# CPU.net
KiCad netlist of a schematic drawn in Altium Designer
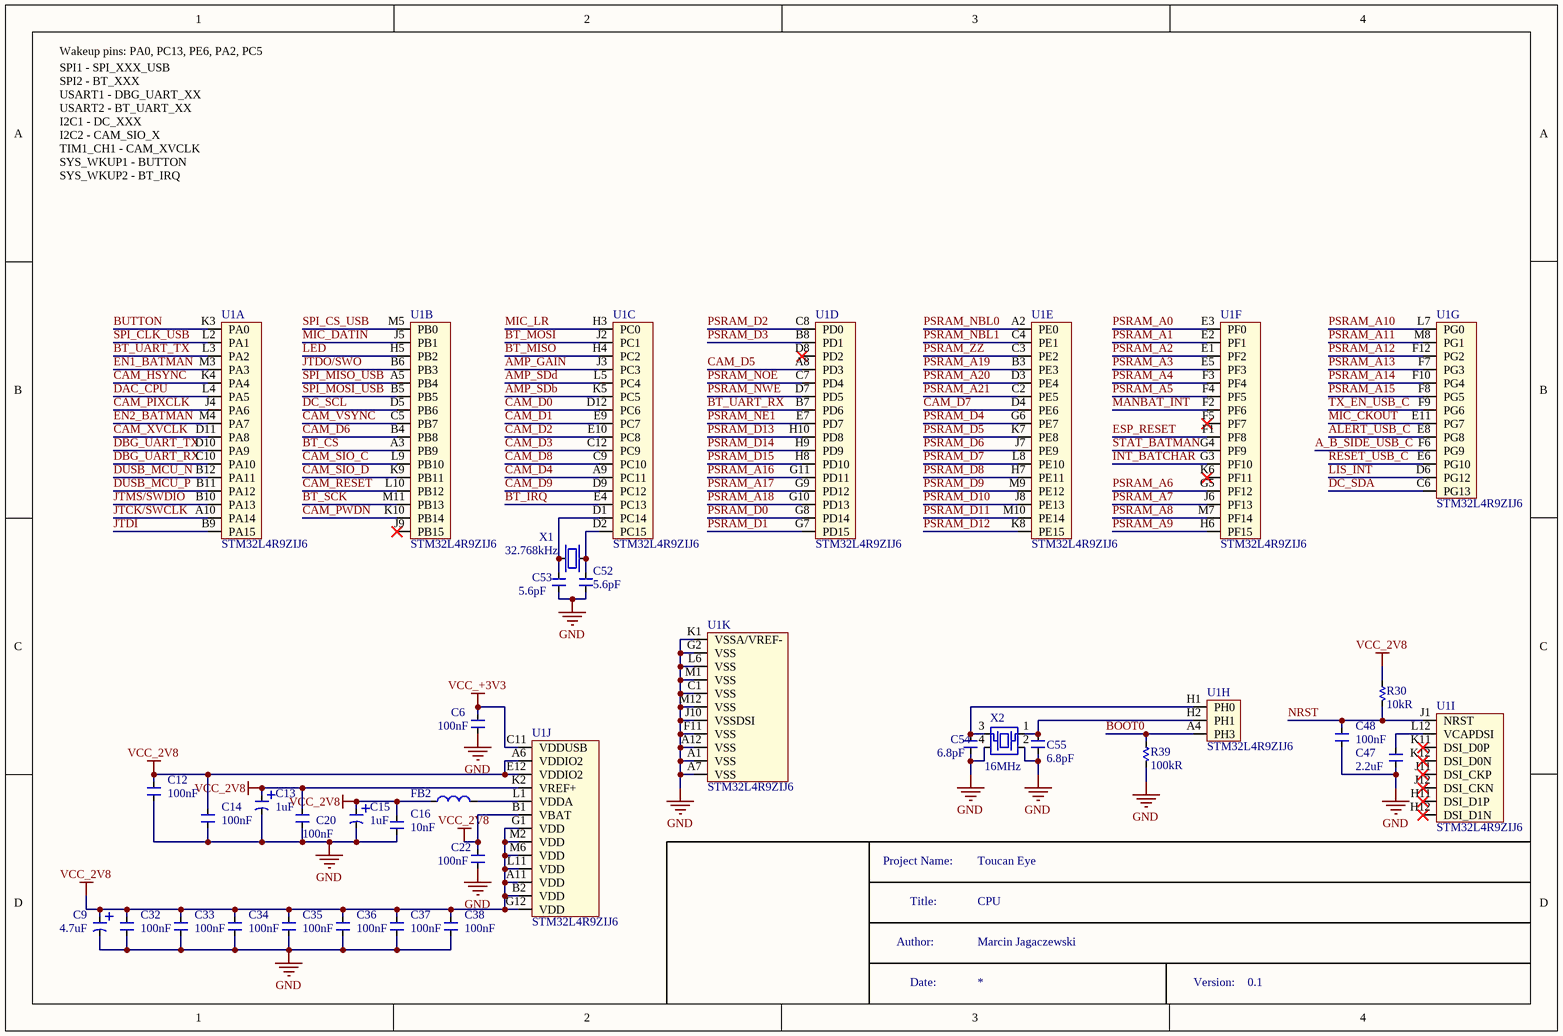
[diagram p0: CPU.SchDoc]

(export (version "E")
  (design (tool "Eeschema 10.0.6"))
  (components
    (comp (ref "C6")
      (value "C0201_100n_GRM033R6YA104KE14D")
      (footprint "C_0201")
      (description "Multilayer Ceramic Capacitors MLCC - SMD/SMT 0201 0.10uF 35volts *Derate Voltage/Temp")
      (fields
        (field (name "MANUFACTURER") "Murata")
        (field (name "MANUFACTURER PART NUMBER") "GRM033R6YA104KE14D")
        (field (name "CAPACITANCE") "100nF")
      )
      (libsource (lib "CAP") (part "C0201_100n_GRM033R6YA104KE14D"))
    )
    (comp (ref "C9")
      (value "C_4.7u_TANTAL_A_TAJA475K016UNJ")
      (footprint "C_3216")
      (description "TANTALUM CHIPS, TAN")
      (fields
        (field (name "MANUFACTURER") "Kyocera AVX")
        (field (name "MANUFACTURER PART NUMBER") "TAJA475K016UNJ")
        (field (name "CAPACITANCE") "4.7uF")
      )
      (libsource (lib "CAP") (part "C_4.7u_TANTAL_A_TAJA475K016UNJ"))
    )
    (comp (ref "C12")
      (value "C0201_100n_GRM033R6YA104KE14D")
      (footprint "C_0201")
      (description "Multilayer Ceramic Capacitors MLCC - SMD/SMT 0201 0.10uF 35volts *Derate Voltage/Temp")
      (fields
        (field (name "MANUFACTURER") "Murata")
        (field (name "MANUFACTURER PART NUMBER") "GRM033R6YA104KE14D")
        (field (name "CAPACITANCE") "100nF")
      )
      (libsource (lib "CAP") (part "C0201_100n_GRM033R6YA104KE14D"))
    )
    (comp (ref "C13")
      (value "C_1u_TANTAL_A_293D105X0025A2TE3")
      (footprint "C_3216")
      (description "CAP TANT 1UF 25V 20% 1206")
      (fields
        (field (name "MANUFACTURER") "Vishay Sprague")
        (field (name "MANUFACTURER PART NUMBER") "293D105X0025A2TE3")
        (field (name "CAPACITANCE") "1uF")
      )
      (libsource (lib "CAP") (part "C_1u_TANTAL_A_293D105X0025A2TE3"))
    )
    (comp (ref "C14")
      (value "C0201_100n_GRM033R6YA104KE14D")
      (footprint "C_0201")
      (description "Multilayer Ceramic Capacitors MLCC - SMD/SMT 0201 0.10uF 35volts *Derate Voltage/Temp")
      (fields
        (field (name "MANUFACTURER") "Murata")
        (field (name "MANUFACTURER PART NUMBER") "GRM033R6YA104KE14D")
        (field (name "CAPACITANCE") "100nF")
      )
      (libsource (lib "CAP") (part "C0201_100n_GRM033R6YA104KE14D"))
    )
    (comp (ref "C15")
      (value "C_1u_TANTAL_A_293D105X0025A2TE3")
      (footprint "C_3216")
      (description "CAP TANT 1UF 25V 20% 1206")
      (fields
        (field (name "MANUFACTURER") "Vishay Sprague")
        (field (name "MANUFACTURER PART NUMBER") "293D105X0025A2TE3")
        (field (name "CAPACITANCE") "1uF")
      )
      (libsource (lib "CAP") (part "C_1u_TANTAL_A_293D105X0025A2TE3"))
    )
    (comp (ref "C16")
      (value "C0201_10n_CGA1A2X7R1A103K030BA")
      (footprint "C_0201")
      (fields
        (field (name "MANUFACTURER") "TDK")
        (field (name "MANUFACTURER PART NUMBER") "CGA1A2X7R1A103K030BA")
        (field (name "TOLERANCE") "10%")
        (field (name "CAPACITANCE") "10nF")
      )
      (libsource (lib "CAP") (part "C0201_10n_CGA1A2X7R1A103K030BA"))
    )
    (comp (ref "C20")
      (value "C0201_100n_GRM033R6YA104KE14D")
      (footprint "C_0201")
      (description "Multilayer Ceramic Capacitors MLCC - SMD/SMT 0201 0.10uF 35volts *Derate Voltage/Temp")
      (fields
        (field (name "MANUFACTURER") "Murata")
        (field (name "MANUFACTURER PART NUMBER") "GRM033R6YA104KE14D")
        (field (name "CAPACITANCE") "100nF")
      )
      (libsource (lib "CAP") (part "C0201_100n_GRM033R6YA104KE14D"))
    )
    (comp (ref "C22")
      (value "C0201_100n_GRM033R6YA104KE14D")
      (footprint "C_0201")
      (description "Multilayer Ceramic Capacitors MLCC - SMD/SMT 0201 0.10uF 35volts *Derate Voltage/Temp")
      (fields
        (field (name "MANUFACTURER") "Murata")
        (field (name "MANUFACTURER PART NUMBER") "GRM033R6YA104KE14D")
        (field (name "CAPACITANCE") "100nF")
      )
      (libsource (lib "CAP") (part "C0201_100n_GRM033R6YA104KE14D"))
    )
    (comp (ref "C32")
      (value "C0201_100n_GRM033R6YA104KE14D")
      (footprint "C_0201")
      (description "Multilayer Ceramic Capacitors MLCC - SMD/SMT 0201 0.10uF 35volts *Derate Voltage/Temp")
      (fields
        (field (name "MANUFACTURER") "Murata")
        (field (name "MANUFACTURER PART NUMBER") "GRM033R6YA104KE14D")
        (field (name "CAPACITANCE") "100nF")
      )
      (libsource (lib "CAP") (part "C0201_100n_GRM033R6YA104KE14D"))
    )
    (comp (ref "C33")
      (value "C0201_100n_GRM033R6YA104KE14D")
      (footprint "C_0201")
      (description "Multilayer Ceramic Capacitors MLCC - SMD/SMT 0201 0.10uF 35volts *Derate Voltage/Temp")
      (fields
        (field (name "MANUFACTURER") "Murata")
        (field (name "MANUFACTURER PART NUMBER") "GRM033R6YA104KE14D")
        (field (name "CAPACITANCE") "100nF")
      )
      (libsource (lib "CAP") (part "C0201_100n_GRM033R6YA104KE14D"))
    )
    (comp (ref "C34")
      (value "C0201_100n_GRM033R6YA104KE14D")
      (footprint "C_0201")
      (description "Multilayer Ceramic Capacitors MLCC - SMD/SMT 0201 0.10uF 35volts *Derate Voltage/Temp")
      (fields
        (field (name "MANUFACTURER") "Murata")
        (field (name "MANUFACTURER PART NUMBER") "GRM033R6YA104KE14D")
        (field (name "CAPACITANCE") "100nF")
      )
      (libsource (lib "CAP") (part "C0201_100n_GRM033R6YA104KE14D"))
    )
    (comp (ref "C35")
      (value "C0201_100n_GRM033R6YA104KE14D")
      (footprint "C_0201")
      (description "Multilayer Ceramic Capacitors MLCC - SMD/SMT 0201 0.10uF 35volts *Derate Voltage/Temp")
      (fields
        (field (name "MANUFACTURER") "Murata")
        (field (name "MANUFACTURER PART NUMBER") "GRM033R6YA104KE14D")
        (field (name "CAPACITANCE") "100nF")
      )
      (libsource (lib "CAP") (part "C0201_100n_GRM033R6YA104KE14D"))
    )
    (comp (ref "C36")
      (value "C0201_100n_GRM033R6YA104KE14D")
      (footprint "C_0201")
      (description "Multilayer Ceramic Capacitors MLCC - SMD/SMT 0201 0.10uF 35volts *Derate Voltage/Temp")
      (fields
        (field (name "MANUFACTURER") "Murata")
        (field (name "MANUFACTURER PART NUMBER") "GRM033R6YA104KE14D")
        (field (name "CAPACITANCE") "100nF")
      )
      (libsource (lib "CAP") (part "C0201_100n_GRM033R6YA104KE14D"))
    )
    (comp (ref "C37")
      (value "C0201_100n_GRM033R6YA104KE14D")
      (footprint "C_0201")
      (description "Multilayer Ceramic Capacitors MLCC - SMD/SMT 0201 0.10uF 35volts *Derate Voltage/Temp")
      (fields
        (field (name "MANUFACTURER") "Murata")
        (field (name "MANUFACTURER PART NUMBER") "GRM033R6YA104KE14D")
        (field (name "CAPACITANCE") "100nF")
      )
      (libsource (lib "CAP") (part "C0201_100n_GRM033R6YA104KE14D"))
    )
    (comp (ref "C38")
      (value "C0201_100n_GRM033R6YA104KE14D")
      (footprint "C_0201")
      (description "Multilayer Ceramic Capacitors MLCC - SMD/SMT 0201 0.10uF 35volts *Derate Voltage/Temp")
      (fields
        (field (name "MANUFACTURER") "Murata")
        (field (name "MANUFACTURER PART NUMBER") "GRM033R6YA104KE14D")
        (field (name "CAPACITANCE") "100nF")
      )
      (libsource (lib "CAP") (part "C0201_100n_GRM033R6YA104KE14D"))
    )
    (comp (ref "C47")
      (value "C0402_2.2u_GRT155R61E225KE13D")
      (footprint "C_0402")
      (description "2.2µF 25V Ceramic Capacitor X5R 0402 (1005 Metric) 0.039\" L x 0.020\" W (1.00mm x 0.50mm)")
      (fields
        (field (name "MANUFACTURER") "Murata")
        (field (name "MANUFACTURER PART NUMBER") "GRT155R61E225KE13D")
        (field (name "CAPACITANCE") "2.2uF")
      )
      (libsource (lib "CAP") (part "C0402_2.2u_GRT155R61E225KE13D"))
    )
    (comp (ref "C48")
      (value "C0201_100n_GRM033R6YA104KE14D")
      (footprint "C_0201")
      (description "Multilayer Ceramic Capacitors MLCC - SMD/SMT 0201 0.10uF 35volts *Derate Voltage/Temp")
      (fields
        (field (name "MANUFACTURER") "Murata")
        (field (name "MANUFACTURER PART NUMBER") "GRM033R6YA104KE14D")
        (field (name "CAPACITANCE") "100nF")
      )
      (libsource (lib "CAP") (part "C0201_100n_GRM033R6YA104KE14D"))
    )
    (comp (ref "C52")
      (value "C0201_5.6pF_GRM0335C1H5R6BA01D")
      (footprint "C_0201")
      (description "Multilayer Ceramic Capacitors MLCC - SMD/SMT 0201 5.6pF 50volts C0G +/-0.1pF")
      (fields
        (field (name "MANUFACTURER") "Murata")
        (field (name "MANUFACTURER PART NUMBER") "GRM0335C1H5R6BA01D")
        (field (name "CAPACITANCE") "5.6pF")
      )
      (libsource (lib "CAP") (part "C0201_5.6pF_GRM0335C1H5R6BA01D"))
    )
    (comp (ref "C53")
      (value "C0201_5.6pF_GRM0335C1H5R6BA01D")
      (footprint "C_0201")
      (description "Multilayer Ceramic Capacitors MLCC - SMD/SMT 0201 5.6pF 50volts C0G +/-0.1pF")
      (fields
        (field (name "MANUFACTURER") "Murata")
        (field (name "MANUFACTURER PART NUMBER") "GRM0335C1H5R6BA01D")
        (field (name "CAPACITANCE") "5.6pF")
      )
      (libsource (lib "CAP") (part "C0201_5.6pF_GRM0335C1H5R6BA01D"))
    )
    (comp (ref "C54")
      (value "C0201_6.8pF_GJM0335C1E6R8CB01D")
      (footprint "C_0201")
      (description "CAP CER 6.8PF 25V NP0 0201")
      (fields
        (field (name "MANUFACTURER") "Murata")
        (field (name "MANUFACTURER PART NUMBER") "GJM0335C1E6R8CB01D")
        (field (name "CAPACITANCE") "6.8pF")
      )
      (libsource (lib "CAP") (part "C0201_6.8pF_GJM0335C1E6R8CB01D"))
    )
    (comp (ref "C55")
      (value "C0201_6.8pF_GJM0335C1E6R8CB01D")
      (footprint "C_0201")
      (description "CAP CER 6.8PF 25V NP0 0201")
      (fields
        (field (name "MANUFACTURER") "Murata")
        (field (name "MANUFACTURER PART NUMBER") "GJM0335C1E6R8CB01D")
        (field (name "CAPACITANCE") "6.8pF")
      )
      (libsource (lib "CAP") (part "C0201_6.8pF_GJM0335C1E6R8CB01D"))
    )
    (comp (ref "FB2")
      (value "BLM15AG121SN1D")
      (footprint "L_0402")
      (description "MURATA         BLM15AG121SN1D             FERRITE BEAD, 0.25OHM, 500MA, 0402")
      (fields (field (name "MANUFACTURER") "Murata") (field (name "TOLERANCE") "25%"))
      (libsource (lib "IND") (part "BLM15AG121SN1D"))
    )
    (comp (ref "R30")
      (value "R0201_10k_ERJ-1GNF1002C")
      (footprint "R_0201")
      (description "RESISTOR, 0201, 0.05W, 1%, 10K")
      (fields
        (field (name "MANUFACTURER") "Panasonic ECG")
        (field (name "MANUFACTURER PART NUMBER") "ERJ-1GNF1002C")
        (field (name "RESISTANCE") "10kR")
      )
      (libsource (lib "RES") (part "R0201_10k_ERJ-1GNF1002C"))
    )
    (comp (ref "R39")
      (value "R0201_100k_CRCW0201100KJN-ED")
      (footprint "R_0201")
      (description "RES SMD 100K OHM 5% 1/20W 0201")
      (fields
        (field (name "MANUFACTURER") "Vishay Dale")
        (field (name "MANUFACTURER PART NUMBER") "CRCW0201100KJN-ED")
        (field (name "RESISTANCE") "100kR")
      )
      (libsource (lib "RES") (part "R0201_100k_CRCW0201100KJN-ED"))
    )
    (comp (ref "U1")
      (value "STM32L4R9ZIJ6")
      (footprint "BGA144C80P12X12_1000X1000X60")
      (libsource (lib "CHIP") (part "STM32L4R9ZIJ6"))
    )
    (comp (ref "X1")
      (value "ABS05-32.768KHZ-9-T")
      (footprint "CRYSTAL_1.6X1")
      (description "32.768kHz ±20ppm Crystal 9pF 90 kOhm -40°C ~ 85°C  Surface Mount 2-SMD")
      (fields
        (field (name "MANUFACTURER") "Abracon")
        (field (name "TOLERANCE") "20ppm")
        (field (name "FREQUENCY") "32.768kHz")
      )
      (libsource (lib "DIO") (part "ABS05-32.768KHZ-9-T"))
    )
    (comp (ref "X2")
      (value "CX2520DB16000F0FDFC1")
      (footprint "CRYSTAL_2.5x2")
      (fields (field (name "MANUFACTURER") "Kyocera AVX") (field (name "FREQ") "16MHz"))
      (libsource (lib "DIO") (part "CX2520DB16000F0FDFC1"))
    )
  )
  (nets
    (net (code "1") (name "/ALERT_USB_C") (class "Default")
      (node (ref "U1") (pin "E8") (pinfunction "PG8_E8") (pintype "passive"))
    )
    (net (code "2") (name "/AMP_GAIN") (class "Default")
      (node (ref "U1") (pin "J3") (pinfunction "PC3_J3") (pintype "passive"))
    )
    (net (code "3") (name "/AMP_~{SDb}") (class "Default")
      (node (ref "U1") (pin "K5") (pinfunction "PC5_K5") (pintype "passive"))
    )
    (net (code "4") (name "/AMP_~{SDd}") (class "Default")
      (node (ref "U1") (pin "L5") (pinfunction "PC4_L5") (pintype "passive"))
    )
    (net (code "5") (name "/A_B_SIDE_USB_C") (class "Default")
      (node (ref "U1") (pin "F6") (pinfunction "PG9_F6") (pintype "passive"))
    )
    (net (code "6") (name "/BOOT0") (class "Default")
      (node (ref "R39") (pin "2") (pinfunction "2_2") (pintype "power_in"))
      (node (ref "U1") (pin "A4") (pinfunction "PH3_A4") (pintype "passive"))
    )
    (net (code "7") (name "/BT_CS") (class "Default")
      (node (ref "U1") (pin "A3") (pinfunction "PB9_A3") (pintype "passive"))
    )
    (net (code "8") (name "/BT_IRQ") (class "Default")
      (node (ref "U1") (pin "E4") (pinfunction "PC13_E4") (pintype "passive"))
    )
    (net (code "9") (name "/BT_MISO") (class "Default")
      (node (ref "U1") (pin "H4") (pinfunction "PC2_H4") (pintype "passive"))
    )
    (net (code "10") (name "/BT_MOSI") (class "Default")
      (node (ref "U1") (pin "J2") (pinfunction "PC1_J2") (pintype "passive"))
    )
    (net (code "11") (name "/BT_SCK") (class "Default")
      (node (ref "U1") (pin "M11") (pinfunction "PB13_M11") (pintype "passive"))
    )
    (net (code "12") (name "/BT_UART_RX") (class "Default")
      (node (ref "U1") (pin "B7") (pinfunction "PD6_B7") (pintype "passive"))
    )
    (net (code "13") (name "/BT_UART_TX") (class "Default")
      (node (ref "U1") (pin "L3") (pinfunction "PA2_L3") (pintype "passive"))
    )
    (net (code "14") (name "/BUTTON") (class "Default")
      (node (ref "U1") (pin "K3") (pinfunction "PA0_K3") (pintype "passive"))
    )
    (net (code "15") (name "/CAM_D0") (class "Default")
      (node (ref "U1") (pin "D12") (pinfunction "PC6_D12") (pintype "passive"))
    )
    (net (code "16") (name "/CAM_D1") (class "Default")
      (node (ref "U1") (pin "E9") (pinfunction "PC7_E9") (pintype "passive"))
    )
    (net (code "17") (name "/CAM_D2") (class "Default")
      (node (ref "U1") (pin "E10") (pinfunction "PC8_E10") (pintype "passive"))
    )
    (net (code "18") (name "/CAM_D3") (class "Default")
      (node (ref "U1") (pin "C12") (pinfunction "PC9_C12") (pintype "passive"))
    )
    (net (code "19") (name "/CAM_D4") (class "Default")
      (node (ref "U1") (pin "A9") (pinfunction "PC11_A9") (pintype "passive"))
    )
    (net (code "20") (name "/CAM_D5") (class "Default")
      (node (ref "U1") (pin "A8") (pinfunction "PD3_A8") (pintype "passive"))
    )
    (net (code "21") (name "/CAM_D6") (class "Default")
      (node (ref "U1") (pin "B4") (pinfunction "PB8_B4") (pintype "passive"))
    )
    (net (code "22") (name "/CAM_D7") (class "Default")
      (node (ref "U1") (pin "D4") (pinfunction "PE6_D4") (pintype "passive"))
    )
    (net (code "23") (name "/CAM_D8") (class "Default")
      (node (ref "U1") (pin "C9") (pinfunction "PC10_C9") (pintype "passive"))
    )
    (net (code "24") (name "/CAM_D9") (class "Default")
      (node (ref "U1") (pin "D9") (pinfunction "PC12_D9") (pintype "passive"))
    )
    (net (code "25") (name "/CAM_HSYNC") (class "Default")
      (node (ref "U1") (pin "K4") (pinfunction "PA4_K4") (pintype "passive"))
    )
    (net (code "26") (name "/CAM_PIXCLK") (class "Default")
      (node (ref "U1") (pin "J4") (pinfunction "PA6_J4") (pintype "passive"))
    )
    (net (code "27") (name "/CAM_PWDN") (class "Default")
      (node (ref "U1") (pin "K10") (pinfunction "PB14_K10") (pintype "passive"))
    )
    (net (code "28") (name "/CAM_RESET") (class "Default")
      (node (ref "U1") (pin "L10") (pinfunction "PB12_L10") (pintype "passive"))
    )
    (net (code "29") (name "/CAM_SIO_C") (class "Default")
      (node (ref "U1") (pin "L9") (pinfunction "PB10_L9") (pintype "passive"))
    )
    (net (code "30") (name "/CAM_SIO_D") (class "Default")
      (node (ref "U1") (pin "K9") (pinfunction "PB11_K9") (pintype "passive"))
    )
    (net (code "31") (name "/CAM_VSYNC") (class "Default")
      (node (ref "U1") (pin "C5") (pinfunction "PB7_C5") (pintype "passive"))
    )
    (net (code "32") (name "/CAM_XVCLK") (class "Default")
      (node (ref "U1") (pin "D11") (pinfunction "PA8_D11") (pintype "passive"))
    )
    (net (code "33") (name "/DAC_CPU") (class "Default")
      (node (ref "U1") (pin "L4") (pinfunction "PA5_L4") (pintype "passive"))
    )
    (net (code "34") (name "/DBG_UART_RX") (class "Default")
      (node (ref "U1") (pin "C10") (pinfunction "PA10_C10") (pintype "passive"))
    )
    (net (code "35") (name "/DBG_UART_TX") (class "Default")
      (node (ref "U1") (pin "D10") (pinfunction "PA9_D10") (pintype "passive"))
    )
    (net (code "36") (name "/DC_SCL") (class "Default")
      (node (ref "U1") (pin "D5") (pinfunction "PB6_D5") (pintype "passive"))
    )
    (net (code "37") (name "/DC_SDA") (class "Default")
      (node (ref "U1") (pin "C6") (pinfunction "PG13_C6") (pintype "passive"))
    )
    (net (code "38") (name "/DUSB_MCU_N") (class "Default")
      (node (ref "U1") (pin "B12") (pinfunction "PA11_B12") (pintype "passive"))
    )
    (net (code "39") (name "/DUSB_MCU_P") (class "Default")
      (node (ref "U1") (pin "B11") (pinfunction "PA12_B11") (pintype "passive"))
    )
    (net (code "40") (name "/EN1_BATMAN") (class "Default")
      (node (ref "U1") (pin "M3") (pinfunction "PA3_M3") (pintype "passive"))
    )
    (net (code "41") (name "/EN2_BATMAN") (class "Default")
      (node (ref "U1") (pin "M4") (pinfunction "PA7_M4") (pintype "passive"))
    )
    (net (code "42") (name "/ESP_RESET") (class "Default")
      (node (ref "U1") (pin "F1") (pinfunction "PF8_F1") (pintype "passive"))
    )
    (net (code "43") (name "/INT_BATCHAR") (class "Default")
      (node (ref "U1") (pin "G3") (pinfunction "PF10_G3") (pintype "passive"))
    )
    (net (code "44") (name "/JTCK{slash}SWCLK") (class "Default")
      (node (ref "U1") (pin "A10") (pinfunction "PA14_A10") (pintype "passive"))
    )
    (net (code "45") (name "/JTDI") (class "Default")
      (node (ref "U1") (pin "B9") (pinfunction "PA15_B9") (pintype "passive"))
    )
    (net (code "46") (name "/JTDO{slash}SWO") (class "Default")
      (node (ref "U1") (pin "B6") (pinfunction "PB3_B6") (pintype "passive"))
    )
    (net (code "47") (name "/JTMS{slash}SWDIO") (class "Default")
      (node (ref "U1") (pin "B10") (pinfunction "PA13_B10") (pintype "passive"))
    )
    (net (code "48") (name "/LED") (class "Default")
      (node (ref "U1") (pin "H5") (pinfunction "PB2_H5") (pintype "passive"))
    )
    (net (code "49") (name "/LIS_INT") (class "Default")
      (node (ref "U1") (pin "D6") (pinfunction "PG12_D6") (pintype "passive"))
    )
    (net (code "50") (name "/MANBAT_INT") (class "Default")
      (node (ref "U1") (pin "F2") (pinfunction "PF6_F2") (pintype "passive"))
    )
    (net (code "51") (name "/MIC_CKOUT") (class "Default")
      (node (ref "U1") (pin "E11") (pinfunction "PG7_E11") (pintype "passive"))
    )
    (net (code "52") (name "/MIC_DATIN") (class "Default")
      (node (ref "U1") (pin "J5") (pinfunction "PB1_J5") (pintype "passive"))
    )
    (net (code "53") (name "/MIC_LR") (class "Default")
      (node (ref "U1") (pin "H3") (pinfunction "PC0_H3") (pintype "passive"))
    )
    (net (code "54") (name "/NRST") (class "Default")
      (node (ref "C48") (pin "2") (pinfunction "2_2") (pintype "passive"))
      (node (ref "R30") (pin "1") (pinfunction "1_1") (pintype "power_in"))
      (node (ref "U1") (pin "J1") (pinfunction "NRST_J1") (pintype "passive"))
    )
    (net (code "55") (name "/PSRAM_A0") (class "Default")
      (node (ref "U1") (pin "E3") (pinfunction "PF0_E3") (pintype "passive"))
    )
    (net (code "56") (name "/PSRAM_A1") (class "Default")
      (node (ref "U1") (pin "E2") (pinfunction "PF1_E2") (pintype "passive"))
    )
    (net (code "57") (name "/PSRAM_A2") (class "Default")
      (node (ref "U1") (pin "E1") (pinfunction "PF2_E1") (pintype "passive"))
    )
    (net (code "58") (name "/PSRAM_A3") (class "Default")
      (node (ref "U1") (pin "E5") (pinfunction "PF3_E5") (pintype "passive"))
    )
    (net (code "59") (name "/PSRAM_A4") (class "Default")
      (node (ref "U1") (pin "F3") (pinfunction "PF4_F3") (pintype "passive"))
    )
    (net (code "60") (name "/PSRAM_A5") (class "Default")
      (node (ref "U1") (pin "F4") (pinfunction "PF5_F4") (pintype "passive"))
    )
    (net (code "61") (name "/PSRAM_A6") (class "Default")
      (node (ref "U1") (pin "G5") (pinfunction "PF12_G5") (pintype "passive"))
    )
    (net (code "62") (name "/PSRAM_A7") (class "Default")
      (node (ref "U1") (pin "J6") (pinfunction "PF13_J6") (pintype "passive"))
    )
    (net (code "63") (name "/PSRAM_A8") (class "Default")
      (node (ref "U1") (pin "M7") (pinfunction "PF14_M7") (pintype "passive"))
    )
    (net (code "64") (name "/PSRAM_A9") (class "Default")
      (node (ref "U1") (pin "H6") (pinfunction "PF15_H6") (pintype "passive"))
    )
    (net (code "65") (name "/PSRAM_A10") (class "Default")
      (node (ref "U1") (pin "L7") (pinfunction "PG0_L7") (pintype "passive"))
    )
    (net (code "66") (name "/PSRAM_A11") (class "Default")
      (node (ref "U1") (pin "M8") (pinfunction "PG1_M8") (pintype "passive"))
    )
    (net (code "67") (name "/PSRAM_A12") (class "Default")
      (node (ref "U1") (pin "F12") (pinfunction "PG2_F12") (pintype "passive"))
    )
    (net (code "68") (name "/PSRAM_A13") (class "Default")
      (node (ref "U1") (pin "F7") (pinfunction "PG3_F7") (pintype "passive"))
    )
    (net (code "69") (name "/PSRAM_A14") (class "Default")
      (node (ref "U1") (pin "F10") (pinfunction "PG4_F10") (pintype "passive"))
    )
    (net (code "70") (name "/PSRAM_A15") (class "Default")
      (node (ref "U1") (pin "F8") (pinfunction "PG5_F8") (pintype "passive"))
    )
    (net (code "71") (name "/PSRAM_A16") (class "Default")
      (node (ref "U1") (pin "G11") (pinfunction "PD11_G11") (pintype "passive"))
    )
    (net (code "72") (name "/PSRAM_A17") (class "Default")
      (node (ref "U1") (pin "G9") (pinfunction "PD12_G9") (pintype "passive"))
    )
    (net (code "73") (name "/PSRAM_A18") (class "Default")
      (node (ref "U1") (pin "G10") (pinfunction "PD13_G10") (pintype "passive"))
    )
    (net (code "74") (name "/PSRAM_A19") (class "Default")
      (node (ref "U1") (pin "B3") (pinfunction "PE3_B3") (pintype "passive"))
    )
    (net (code "75") (name "/PSRAM_A20") (class "Default")
      (node (ref "U1") (pin "D3") (pinfunction "PE4_D3") (pintype "passive"))
    )
    (net (code "76") (name "/PSRAM_A21") (class "Default")
      (node (ref "U1") (pin "C2") (pinfunction "PE5_C2") (pintype "passive"))
    )
    (net (code "77") (name "/PSRAM_D0") (class "Default")
      (node (ref "U1") (pin "G8") (pinfunction "PD14_G8") (pintype "passive"))
    )
    (net (code "78") (name "/PSRAM_D1") (class "Default")
      (node (ref "U1") (pin "G7") (pinfunction "PD15_G7") (pintype "passive"))
    )
    (net (code "79") (name "/PSRAM_D2") (class "Default")
      (node (ref "U1") (pin "C8") (pinfunction "PD0_C8") (pintype "passive"))
    )
    (net (code "80") (name "/PSRAM_D3") (class "Default")
      (node (ref "U1") (pin "B8") (pinfunction "PD1_B8") (pintype "passive"))
    )
    (net (code "81") (name "/PSRAM_D4") (class "Default")
      (node (ref "U1") (pin "G6") (pinfunction "PE7_G6") (pintype "passive"))
    )
    (net (code "82") (name "/PSRAM_D5") (class "Default")
      (node (ref "U1") (pin "K7") (pinfunction "PE8_K7") (pintype "passive"))
    )
    (net (code "83") (name "/PSRAM_D6") (class "Default")
      (node (ref "U1") (pin "J7") (pinfunction "PE9_J7") (pintype "passive"))
    )
    (net (code "84") (name "/PSRAM_D7") (class "Default")
      (node (ref "U1") (pin "L8") (pinfunction "PE10_L8") (pintype "passive"))
    )
    (net (code "85") (name "/PSRAM_D8") (class "Default")
      (node (ref "U1") (pin "H7") (pinfunction "PE11_H7") (pintype "passive"))
    )
    (net (code "86") (name "/PSRAM_D9") (class "Default")
      (node (ref "U1") (pin "M9") (pinfunction "PE12_M9") (pintype "passive"))
    )
    (net (code "87") (name "/PSRAM_D10") (class "Default")
      (node (ref "U1") (pin "J8") (pinfunction "PE13_J8") (pintype "passive"))
    )
    (net (code "88") (name "/PSRAM_D11") (class "Default")
      (node (ref "U1") (pin "M10") (pinfunction "PE14_M10") (pintype "passive"))
    )
    (net (code "89") (name "/PSRAM_D12") (class "Default")
      (node (ref "U1") (pin "K8") (pinfunction "PE15_K8") (pintype "passive"))
    )
    (net (code "90") (name "/PSRAM_D13") (class "Default")
      (node (ref "U1") (pin "H10") (pinfunction "PD8_H10") (pintype "passive"))
    )
    (net (code "91") (name "/PSRAM_D14") (class "Default")
      (node (ref "U1") (pin "H9") (pinfunction "PD9_H9") (pintype "passive"))
    )
    (net (code "92") (name "/PSRAM_D15") (class "Default")
      (node (ref "U1") (pin "H8") (pinfunction "PD10_H8") (pintype "passive"))
    )
    (net (code "93") (name "/PSRAM_NBL0") (class "Default")
      (node (ref "U1") (pin "A2") (pinfunction "PE0_A2") (pintype "passive"))
    )
    (net (code "94") (name "/PSRAM_NBL1") (class "Default")
      (node (ref "U1") (pin "C4") (pinfunction "PE1_C4") (pintype "passive"))
    )
    (net (code "95") (name "/PSRAM_NE1") (class "Default")
      (node (ref "U1") (pin "E7") (pinfunction "PD7_E7") (pintype "passive"))
    )
    (net (code "96") (name "/PSRAM_NOE") (class "Default")
      (node (ref "U1") (pin "C7") (pinfunction "PD4_C7") (pintype "passive"))
    )
    (net (code "97") (name "/PSRAM_NWE") (class "Default")
      (node (ref "U1") (pin "D7") (pinfunction "PD5_D7") (pintype "passive"))
    )
    (net (code "98") (name "/PSRAM_ZZ") (class "Default")
      (node (ref "U1") (pin "C3") (pinfunction "PE2_C3") (pintype "passive"))
    )
    (net (code "99") (name "/RESET_USB_C") (class "Default")
      (node (ref "U1") (pin "E6") (pinfunction "PG10_E6") (pintype "passive"))
    )
    (net (code "100") (name "/SPI_CLK_USB") (class "Default")
      (node (ref "U1") (pin "L2") (pinfunction "PA1_L2") (pintype "passive"))
    )
    (net (code "101") (name "/SPI_CS_USB") (class "Default")
      (node (ref "U1") (pin "M5") (pinfunction "PB0_M5") (pintype "passive"))
    )
    (net (code "102") (name "/SPI_MISO_USB") (class "Default")
      (node (ref "U1") (pin "A5") (pinfunction "PB4_A5") (pintype "passive"))
    )
    (net (code "103") (name "/SPI_MOSI_USB") (class "Default")
      (node (ref "U1") (pin "B5") (pinfunction "PB5_B5") (pintype "passive"))
    )
    (net (code "104") (name "/STAT_BATMAN") (class "Default")
      (node (ref "U1") (pin "G4") (pinfunction "PF9_G4") (pintype "passive"))
    )
    (net (code "105") (name "/TX_EN_USB_C") (class "Default")
      (node (ref "U1") (pin "F9") (pinfunction "PG6_F9") (pintype "passive"))
    )
    (net (code "106") (name "GND") (class "Default")
      (node (ref "C12") (pin "2") (pinfunction "2_2") (pintype "passive"))
      (node (ref "C13") (pin "2") (pinfunction "2_2") (pintype "passive"))
      (node (ref "C14") (pin "2") (pinfunction "2_2") (pintype "passive"))
      (node (ref "C15") (pin "2") (pinfunction "2_2") (pintype "passive"))
      (node (ref "C16") (pin "2") (pinfunction "2_2") (pintype "passive"))
      (node (ref "C20") (pin "2") (pinfunction "2_2") (pintype "passive"))
      (node (ref "C22") (pin "1") (pinfunction "1_1") (pintype "passive"))
      (node (ref "C32") (pin "1") (pinfunction "1_1") (pintype "passive"))
      (node (ref "C33") (pin "1") (pinfunction "1_1") (pintype "passive"))
      (node (ref "C34") (pin "1") (pinfunction "1_1") (pintype "passive"))
      (node (ref "C35") (pin "1") (pinfunction "1_1") (pintype "passive"))
      (node (ref "C36") (pin "1") (pinfunction "1_1") (pintype "passive"))
      (node (ref "C37") (pin "1") (pinfunction "1_1") (pintype "passive"))
      (node (ref "C38") (pin "1") (pinfunction "1_1") (pintype "passive"))
      (node (ref "C47") (pin "1") (pinfunction "1_1") (pintype "passive"))
      (node (ref "C48") (pin "1") (pinfunction "1_1") (pintype "passive"))
      (node (ref "C52") (pin "1") (pinfunction "1_1") (pintype "passive"))
      (node (ref "C53") (pin "2") (pinfunction "2_2") (pintype "passive"))
      (node (ref "C54") (pin "2") (pinfunction "2_2") (pintype "passive"))
      (node (ref "C55") (pin "1") (pinfunction "1_1") (pintype "passive"))
      (node (ref "C6") (pin "2") (pinfunction "2_2") (pintype "passive"))
      (node (ref "C9") (pin "2") (pinfunction "2_2") (pintype "passive"))
      (node (ref "R39") (pin "1") (pinfunction "1_1") (pintype "power_in"))
      (node (ref "U1") (pin "A1") (pinfunction "VSS_A1") (pintype "passive"))
      (node (ref "U1") (pin "A12") (pinfunction "VSS_A12") (pintype "passive"))
      (node (ref "U1") (pin "A7") (pinfunction "VSS_A7") (pintype "passive"))
      (node (ref "U1") (pin "C1") (pinfunction "VSS_C1") (pintype "passive"))
      (node (ref "U1") (pin "F11") (pinfunction "VSS_F11") (pintype "passive"))
      (node (ref "U1") (pin "G2") (pinfunction "VSS_G2") (pintype "passive"))
      (node (ref "U1") (pin "J10") (pinfunction "VSSDSI_J10") (pintype "passive"))
      (node (ref "U1") (pin "K1") (pinfunction "VSSA/VREF-_K1") (pintype "passive"))
      (node (ref "U1") (pin "L6") (pinfunction "VSS_L6") (pintype "passive"))
      (node (ref "U1") (pin "M1") (pinfunction "VSS_M1") (pintype "passive"))
      (node (ref "U1") (pin "M12") (pinfunction "VSS_M12") (pintype "passive"))
      (node (ref "X2") (pin "2") (pinfunction "2_2") (pintype "power_in"))
      (node (ref "X2") (pin "4") (pinfunction "4_4") (pintype "power_in"))
    )
    (net (code "107") (name "Net-(U1C-PC14)") (class "Default")
      (node (ref "C53") (pin "1") (pinfunction "1_1") (pintype "passive"))
      (node (ref "U1") (pin "D1") (pinfunction "PC14_D1") (pintype "passive"))
      (node (ref "X1") (pin "1") (pinfunction "1_1") (pintype "power_in"))
    )
    (net (code "108") (name "Net-(U1C-PC15)") (class "Default")
      (node (ref "C52") (pin "2") (pinfunction "2_2") (pintype "passive"))
      (node (ref "U1") (pin "D2") (pinfunction "PC15_D2") (pintype "passive"))
      (node (ref "X1") (pin "2") (pinfunction "2_2") (pintype "power_in"))
    )
    (net (code "109") (name "Net-(U1H-PH0)") (class "Default")
      (node (ref "C54") (pin "1") (pinfunction "1_1") (pintype "passive"))
      (node (ref "U1") (pin "H1") (pinfunction "PH0_H1") (pintype "passive"))
      (node (ref "X2") (pin "3") (pinfunction "3_3") (pintype "power_in"))
    )
    (net (code "110") (name "Net-(U1H-PH1)") (class "Default")
      (node (ref "C55") (pin "2") (pinfunction "2_2") (pintype "passive"))
      (node (ref "U1") (pin "H2") (pinfunction "PH1_H2") (pintype "passive"))
      (node (ref "X2") (pin "1") (pinfunction "1_1") (pintype "power_in"))
    )
    (net (code "111") (name "Net-(U1I-VCAPDSI)") (class "Default")
      (node (ref "C47") (pin "2") (pinfunction "2_2") (pintype "passive"))
      (node (ref "U1") (pin "L12") (pinfunction "VCAPDSI_L12") (pintype "passive"))
    )
    (net (code "112") (name "Net-(U1J-VDDA)") (class "Default")
      (node (ref "FB2") (pin "2") (pinfunction "Vcc_2") (pintype "passive"))
      (node (ref "U1") (pin "L1") (pinfunction "VDDA_L1") (pintype "passive"))
    )
    (net (code "113") (name "VCC_+3V3") (class "Default")
      (node (ref "C6") (pin "1") (pinfunction "1_1") (pintype "passive"))
      (node (ref "U1") (pin "C11") (pinfunction "VDDUSB_C11") (pintype "passive"))
    )
    (net (code "114") (name "VCC_2V8") (class "Default")
      (node (ref "C12") (pin "1") (pinfunction "1_1") (pintype "passive"))
      (node (ref "C13") (pin "1") (pinfunction "1_1") (pintype "passive"))
      (node (ref "C14") (pin "1") (pinfunction "1_1") (pintype "passive"))
      (node (ref "C15") (pin "1") (pinfunction "1_1") (pintype "passive"))
      (node (ref "C16") (pin "1") (pinfunction "1_1") (pintype "passive"))
      (node (ref "C20") (pin "1") (pinfunction "1_1") (pintype "passive"))
      (node (ref "C22") (pin "2") (pinfunction "2_2") (pintype "passive"))
      (node (ref "C32") (pin "2") (pinfunction "2_2") (pintype "passive"))
      (node (ref "C33") (pin "2") (pinfunction "2_2") (pintype "passive"))
      (node (ref "C34") (pin "2") (pinfunction "2_2") (pintype "passive"))
      (node (ref "C35") (pin "2") (pinfunction "2_2") (pintype "passive"))
      (node (ref "C36") (pin "2") (pinfunction "2_2") (pintype "passive"))
      (node (ref "C37") (pin "2") (pinfunction "2_2") (pintype "passive"))
      (node (ref "C38") (pin "2") (pinfunction "2_2") (pintype "passive"))
      (node (ref "C9") (pin "1") (pinfunction "1_1") (pintype "passive"))
      (node (ref "FB2") (pin "1") (pinfunction "Vcc_1") (pintype "passive"))
      (node (ref "R30") (pin "2") (pinfunction "2_2") (pintype "power_in"))
      (node (ref "U1") (pin "A11") (pinfunction "VDD_A11") (pintype "passive"))
      (node (ref "U1") (pin "A6") (pinfunction "VDDIO2_A6") (pintype "passive"))
      (node (ref "U1") (pin "B1") (pinfunction "VBAT_B1") (pintype "passive"))
      (node (ref "U1") (pin "B2") (pinfunction "VDD_B2") (pintype "passive"))
      (node (ref "U1") (pin "E12") (pinfunction "VDDIO2_E12") (pintype "passive"))
      (node (ref "U1") (pin "G1") (pinfunction "VDD_G1") (pintype "passive"))
      (node (ref "U1") (pin "G12") (pinfunction "VDD_G12") (pintype "passive"))
      (node (ref "U1") (pin "K2") (pinfunction "VREF+_K2") (pintype "passive"))
      (node (ref "U1") (pin "L11") (pinfunction "VDD_L11") (pintype "passive"))
      (node (ref "U1") (pin "M2") (pinfunction "VDD_M2") (pintype "passive"))
      (node (ref "U1") (pin "M6") (pinfunction "VDD_M6") (pintype "passive"))
    )
    (net (code "115") (name "unconnected-(U1B-PB15-PadJ9)") (class "Default")
      (node (ref "U1") (pin "J9") (pinfunction "PB15_J9") (pintype "passive+no_connect"))
    )
    (net (code "116") (name "unconnected-(U1D-PD2-PadD8)") (class "Default")
      (node (ref "U1") (pin "D8") (pinfunction "PD2_D8") (pintype "passive+no_connect"))
    )
    (net (code "117") (name "unconnected-(U1F-PF7-PadF5)") (class "Default")
      (node (ref "U1") (pin "F5") (pinfunction "PF7_F5") (pintype "passive+no_connect"))
    )
    (net (code "118") (name "unconnected-(U1F-PF11-PadK6)") (class "Default")
      (node (ref "U1") (pin "K6") (pinfunction "PF11_K6") (pintype "passive+no_connect"))
    )
    (net (code "119") (name "unconnected-(U1I-DSI_CKN-PadJ12)") (class "Default")
      (node (ref "U1") (pin "J12") (pinfunction "DSI_CKN_J12") (pintype "passive+no_connect"))
    )
    (net (code "120") (name "unconnected-(U1I-DSI_CKP-PadJ11)") (class "Default")
      (node (ref "U1") (pin "J11") (pinfunction "DSI_CKP_J11") (pintype "passive+no_connect"))
    )
    (net (code "121") (name "unconnected-(U1I-DSI_D0N-PadK12)") (class "Default")
      (node (ref "U1") (pin "K12") (pinfunction "DSI_D0N_K12") (pintype "passive+no_connect"))
    )
    (net (code "122") (name "unconnected-(U1I-DSI_D0P-PadK11)") (class "Default")
      (node (ref "U1") (pin "K11") (pinfunction "DSI_D0P_K11") (pintype "passive+no_connect"))
    )
    (net (code "123") (name "unconnected-(U1I-DSI_D1N-PadH12)") (class "Default")
      (node (ref "U1") (pin "H12") (pinfunction "DSI_D1N_H12") (pintype "passive+no_connect"))
    )
    (net (code "124") (name "unconnected-(U1I-DSI_D1P-PadH11)") (class "Default")
      (node (ref "U1") (pin "H11") (pinfunction "DSI_D1P_H11") (pintype "passive+no_connect"))
    )
  )
)
